# E17-04_IMD.net
KiCad netlist of a schematic drawn in Altium Designer
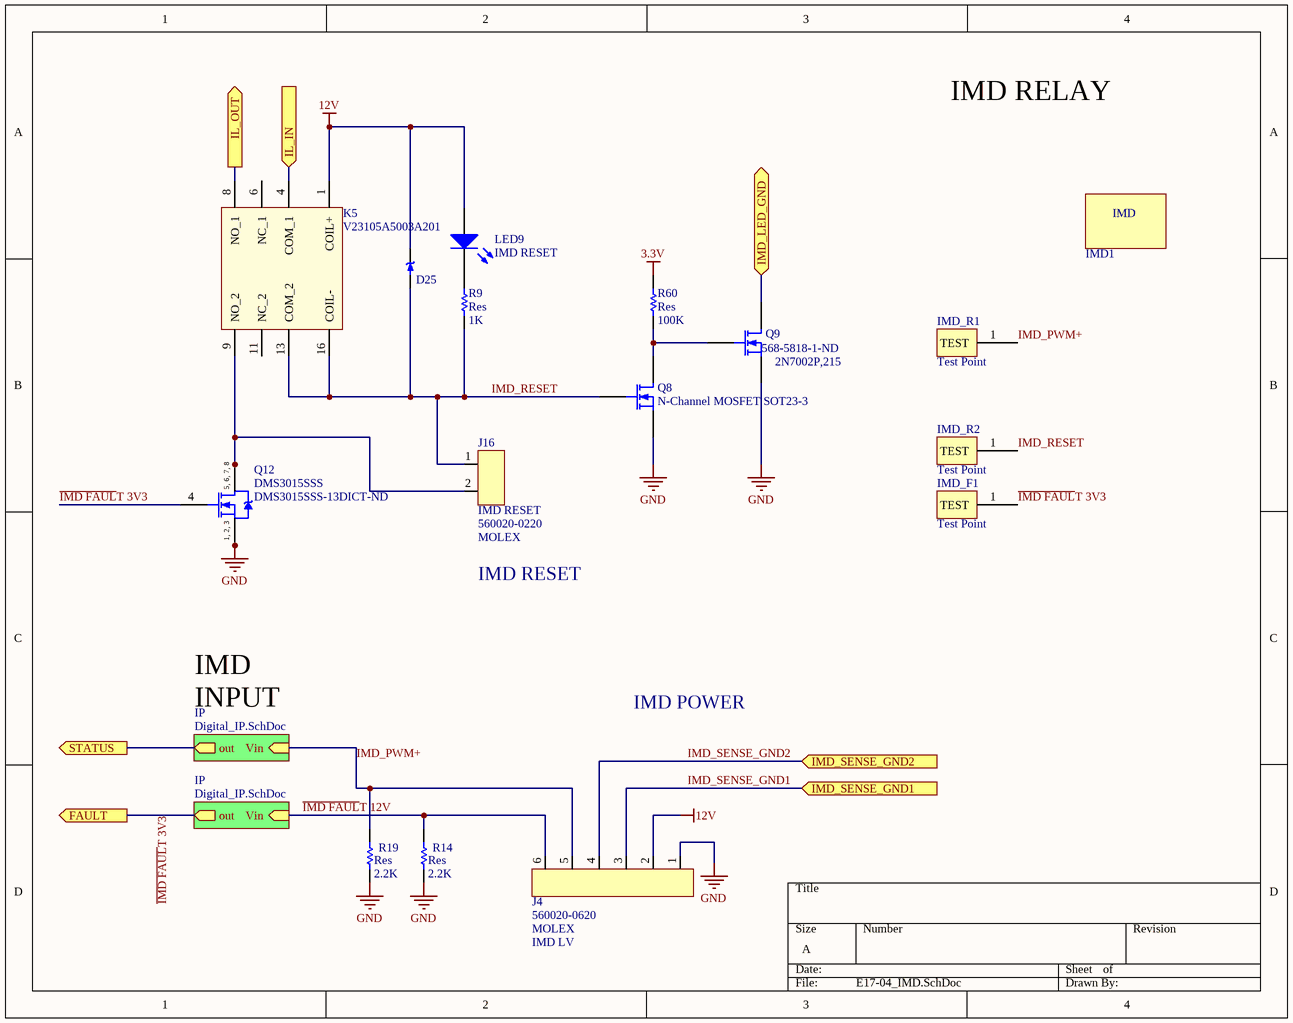
[diagram p0: E17-04_IMD.SchDoc]

(export (version "E")
  (design (tool "Eeschema 10.0.6"))
  (components
    (comp (ref "D25")
      (value "PMEG4010ET")
      (footprint "SOT23-3")
      (description "SCHOTTKY RECT 40V 1A SOT-23")
      (libsource (lib "Diodes") (part "PMEG4010ET"))
    )
    (comp (ref "IMD1")
      (value "ISOMETER IR155-3203")
      (footprint "ISOMETER_IR155")
      (libsource (lib "Modules") (part "Bender ISOMETER IR155-3203"))
    )
    (comp (ref "IMD_F1")
      (value "Test Point")
      (footprint "TEST POINT 5000K")
      (description "5000-5004, 5015-5019 Keystone Electronics")
      (libsource (lib "Mechanical Devices") (part "Test Point"))
    )
    (comp (ref "IMD_R1")
      (value "Test Point")
      (footprint "TEST POINT 5000K")
      (description "5000-5004, 5015-5019 Keystone Electronics")
      (libsource (lib "Mechanical Devices") (part "Test Point"))
    )
    (comp (ref "IMD_R2")
      (value "Test Point")
      (footprint "TEST POINT 5000K")
      (description "5000-5004, 5015-5019 Keystone Electronics")
      (libsource (lib "Mechanical Devices") (part "Test Point"))
    )
    (comp (ref "J4")
      (value "IMD LV")
      (footprint "MOLEX_DURACLIK_6 NAT VERT")
      (description "MOLEX DURACLIK 6-PIN VERT NAT")
      (fields
        (field (name "VOLTAGE") "125")
        (field (name "MPN") "560020-0620")
        (field (name "MANUFACTURER") "MOLEX")
      )
      (libsource (lib "Molex_DuraClik") (part "560020-0620"))
    )
    (comp (ref "J16")
      (value "IMD RESET")
      (footprint "MOLEX_DURACLIK_2 NAT VERT")
      (description "MOLEX DURACLIK 2-PIN VERT NAT")
      (fields
        (field (name "VOLTAGE") "125")
        (field (name "MPN") "560020-0220")
        (field (name "MANUFACTURER") "MOLEX")
      )
      (libsource (lib "Molex_DuraClik") (part "560020-0220"))
    )
    (comp (ref "K5")
      (value "K_V23105A5003A201")
      (footprint "K_V23105A5003A201")
      (description "RELAY DPDT 12V/12.5mA, 220V/3A")
      (fields (field (name "MFG") "TE") (field (name "MFG_PN") "V23105A5003A201"))
      (libsource (lib "Relays") (part "K_V23105A5003A201"))
    )
    (comp (ref "LED9")
      (value "IMD RESET")
      (footprint "155124VS73200")
      (description "Right Angle SMD Green 2V")
      (fields
        (field (name "MANUFACTURER") "Wurth Electronics Inc")
        (field (name "MANUFACTURER PART NUMBER") "155124VS73200")
      )
      (libsource (lib "LEDs") (part "155124VS73200"))
    )
    (comp (ref "Q8")
      (value "N-Channel MOSFET SOT23-3")
      (footprint "SOT23-3")
      (libsource (lib "Transistors") (part "MOSFET-N SOT23-3"))
    )
    (comp (ref "Q9")
      (value "2N7002P,215")
      (footprint "SOT23-3")
      (description "N-Channel Enhancement Mode Vertical DMOS FET")
      (fields (field (name "SUPPLIER PART NUMBER 1") "568-5818-1-ND"))
      (libsource (lib "Transistors") (part "2N7002P,215"))
    )
    (comp (ref "Q12")
      (value "DMS3015SSS")
      (footprint "E17-04-PCB:SOIC-8-150")
      (description "N-Channel Power MOSFET")
      (fields (field (name "SUPPLIER PART NUMBER 1") "DMS3015SSS-13DICT-ND"))
      (libsource (lib "Transistors") (part "DMS3015SSS"))
    )
    (comp (ref "R9")
      (value "Res")
      (footprint "2012[0805]")
      (description "Surface Mount Resistor")
      (fields (field (name "ALTIUM_VALUE") "1K") (field (name "PUBLISHER") "Altium Limited"))
      (libsource (lib "Resistors") (part "Res"))
    )
    (comp (ref "R14")
      (value "Res")
      (footprint "2012[0805]")
      (description "Surface Mount Resistor")
      (fields (field (name "ALTIUM_VALUE") "2.2K") (field (name "PUBLISHER") "Altium Limited"))
      (libsource (lib "Resistors") (part "Res"))
    )
    (comp (ref "R19")
      (value "Res")
      (footprint "2012[0805]")
      (description "Surface Mount Resistor")
      (fields (field (name "ALTIUM_VALUE") "2.2K") (field (name "PUBLISHER") "Altium Limited"))
      (libsource (lib "Resistors") (part "Res"))
    )
    (comp (ref "R60")
      (value "Res")
      (footprint "2012[0805]")
      (description "Surface Mount Resistor")
      (fields (field (name "ALTIUM_VALUE") "100K") (field (name "PUBLISHER") "Altium Limited"))
      (libsource (lib "Resistors") (part "Res"))
    )
  )
  (nets
    (net (code "1") (name "/IL_IN") (class "Default")
      (node (ref "K5") (pin "4") (pinfunction "COM_1_4") (pintype "passive"))
    )
    (net (code "2") (name "/IL_OUT") (class "Default")
      (node (ref "K5") (pin "8") (pinfunction "NO_1_8") (pintype "passive"))
    )
    (net (code "3") (name "/IMD_LED_GND") (class "Default")
      (node (ref "Q9") (pin "3") (pinfunction "D_3") (pintype "passive"))
    )
    (net (code "4") (name "/IMD_PWM+") (class "Default")
      (node (ref "IMD_R1") (pin "1") (pinfunction "TEST_1") (pintype "passive"))
      (node (ref "J4") (pin "5") (pinfunction "5_5") (pintype "passive"))
      (node (ref "R19") (pin "1") (pinfunction "1_1") (pintype "passive"))
    )
    (net (code "5") (name "/IMD_RESET") (class "Default")
      (node (ref "D25") (pin "1") (pinfunction "1_1") (pintype "passive"))
      (node (ref "IMD_R2") (pin "1") (pinfunction "TEST_1") (pintype "passive"))
      (node (ref "J16") (pin "1") (pinfunction "1_1") (pintype "passive"))
      (node (ref "K5") (pin "13") (pinfunction "COM_2_13") (pintype "passive"))
      (node (ref "K5") (pin "16") (pinfunction "COIL-_16") (pintype "passive"))
      (node (ref "Q8") (pin "1") (pinfunction "G_1") (pintype "passive"))
      (node (ref "R9") (pin "2") (pinfunction "2_2") (pintype "passive"))
    )
    (net (code "6") (name "/IMD_SENSE_GND1") (class "Default")
      (node (ref "J4") (pin "3") (pinfunction "3_3") (pintype "passive"))
    )
    (net (code "7") (name "/IMD_SENSE_GND2") (class "Default")
      (node (ref "J4") (pin "4") (pinfunction "4_4") (pintype "passive"))
    )
    (net (code "9") (name "/~{IMD FAUL}T 3V3") (class "Default")
      (node (ref "IMD_F1") (pin "1") (pinfunction "TEST_1") (pintype "passive"))
      (node (ref "Q12") (pin "4") (pinfunction "G_4") (pintype "passive"))
    )
    (net (code "10") (name "/~{IMD FAUL}T 12V") (class "Default")
      (node (ref "J4") (pin "6") (pinfunction "6_6") (pintype "passive"))
      (node (ref "R14") (pin "1") (pinfunction "1_1") (pintype "passive"))
    )
    (net (code "11") (name "3.3V") (class "Default")
      (node (ref "R60") (pin "1") (pinfunction "1_1") (pintype "passive"))
    )
    (net (code "12") (name "12V") (class "Default")
      (node (ref "D25") (pin "3") (pinfunction "3_3") (pintype "passive"))
      (node (ref "J4") (pin "2") (pinfunction "2_2") (pintype "passive"))
      (node (ref "K5") (pin "1") (pinfunction "COIL+_1") (pintype "passive"))
      (node (ref "LED9") (pin "2") (pinfunction "2_2") (pintype "passive"))
    )
    (net (code "13") (name "GND") (class "Default")
      (node (ref "J4") (pin "1") (pinfunction "1_1") (pintype "passive"))
      (node (ref "Q12") (pin "1") (pinfunction "S_1") (pintype "passive"))
      (node (ref "Q12") (pin "2") (pinfunction "S_2") (pintype "passive"))
      (node (ref "Q12") (pin "3") (pinfunction "S_3") (pintype "passive"))
      (node (ref "Q8") (pin "2") (pinfunction "S_2") (pintype "passive"))
      (node (ref "Q9") (pin "2") (pinfunction "S_2") (pintype "passive"))
      (node (ref "R14") (pin "2") (pinfunction "2_2") (pintype "passive"))
      (node (ref "R19") (pin "2") (pinfunction "2_2") (pintype "passive"))
    )
    (net (code "14") (name "Net-(K5-NO_2)") (class "Default")
      (node (ref "J16") (pin "2") (pinfunction "2_2") (pintype "passive"))
      (node (ref "K5") (pin "9") (pinfunction "NO_2_9") (pintype "passive"))
      (node (ref "Q12") (pin "5") (pinfunction "D_5") (pintype "passive"))
      (node (ref "Q12") (pin "6") (pinfunction "D_6") (pintype "passive"))
      (node (ref "Q12") (pin "7") (pinfunction "D_7") (pintype "passive"))
      (node (ref "Q12") (pin "8") (pinfunction "D_8") (pintype "passive"))
    )
    (net (code "15") (name "Net-(LED9-Pad1)") (class "Default")
      (node (ref "LED9") (pin "1") (pinfunction "1_1") (pintype "passive"))
      (node (ref "R9") (pin "1") (pinfunction "1_1") (pintype "passive"))
    )
    (net (code "16") (name "Net-(Q8-D)") (class "Default")
      (node (ref "Q8") (pin "3") (pinfunction "D_3") (pintype "passive"))
      (node (ref "Q9") (pin "1") (pinfunction "G_1") (pintype "passive"))
      (node (ref "R60") (pin "2") (pinfunction "2_2") (pintype "passive"))
    )
    (net (code "17") (name "unconnected-(K5-NC_1-Pad6)") (class "Default")
      (node (ref "K5") (pin "6") (pinfunction "NC_1_6") (pintype "passive"))
    )
    (net (code "18") (name "unconnected-(K5-NC_2-Pad11)") (class "Default")
      (node (ref "K5") (pin "11") (pinfunction "NC_2_11") (pintype "passive"))
    )
  )
)
